# ZATININHO_V_1.net
KiCad netlist of a schematic drawn in EAGLE
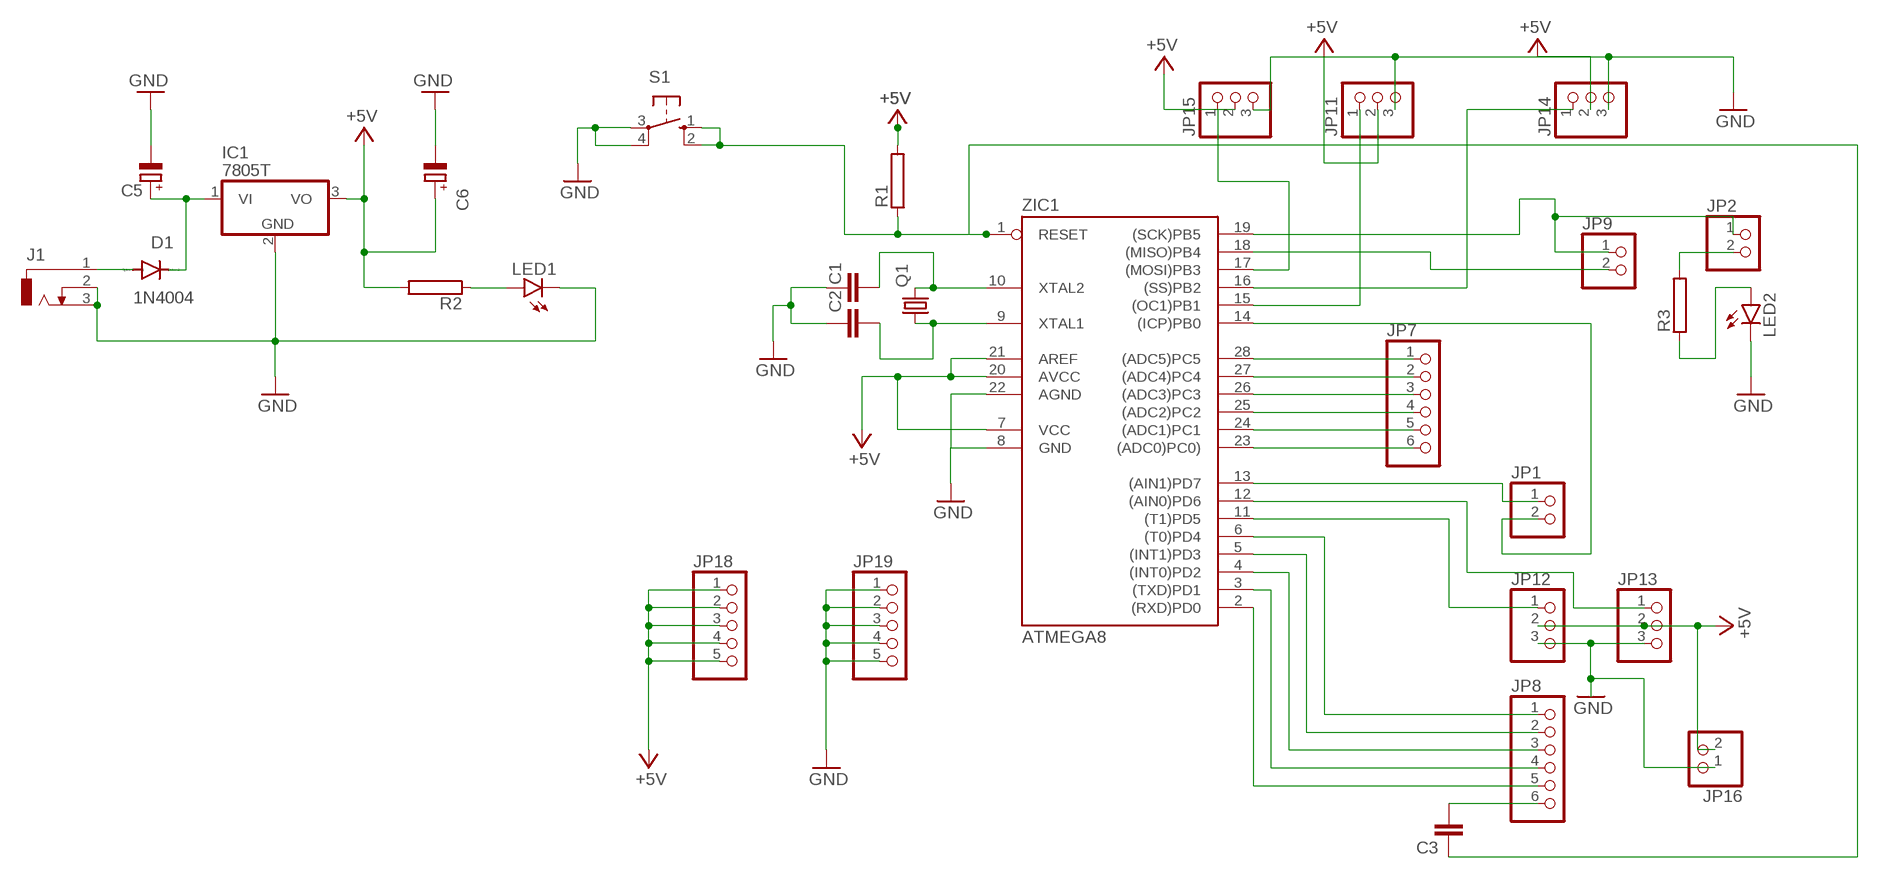
[diagram p0: schematic, sheet 1]

(export (version "E")
  (design (tool "Eeschema 10.0.6"))
  (components
    (comp (ref "C1")
      (value "C2.5/2")
      (footprint "eagle-import:C2.5-2")
      (libsource (lib "eagle-import") (part "C2.5/2"))
    )
    (comp (ref "C2")
      (value "C2.5/2")
      (footprint "eagle-import:C2.5-2")
      (libsource (lib "eagle-import") (part "C2.5/2"))
    )
    (comp (ref "C3")
      (value "C2,5-3")
      (footprint "eagle-import:C2.5-3")
      (libsource (lib "eagle-import") (part "C2,5-3"))
    )
    (comp (ref "C5")
      (value "CPOL-EUE2,5-6E")
      (footprint "eagle-import:E2,5-6E")
      (libsource (lib "eagle-import") (part "CPOL-EUE2,5-6E"))
    )
    (comp (ref "C6")
      (value "CPOL-EUE2,5-6E")
      (footprint "eagle-import:E2,5-6E")
      (libsource (lib "eagle-import") (part "CPOL-EUE2,5-6E"))
    )
    (comp (ref "D1")
      (value "1N4004")
      (footprint "eagle-import:DO41-10")
      (libsource (lib "eagle-import") (part "1N4004"))
    )
    (comp (ref "IC1")
      (value "7805T")
      (footprint "eagle-import:TO220H")
      (libsource (lib "eagle-import") (part "78T05"))
    )
    (comp (ref "J1")
      (value "DCJ0303")
      (footprint "eagle-import:DCJ0303")
      (libsource (lib "eagle-import") (part "DCJ0303"))
    )
    (comp (ref "JP1")
      (value "PINHD-1X2")
      (footprint "eagle-import:1X02")
      (libsource (lib "eagle-import") (part "PINHD-1X2"))
    )
    (comp (ref "JP2")
      (value "PINHD-1X2")
      (footprint "eagle-import:1X02")
      (libsource (lib "eagle-import") (part "PINHD-1X2"))
    )
    (comp (ref "JP7")
      (value "PINHD-1X6")
      (footprint "eagle-import:1X06")
      (libsource (lib "eagle-import") (part "PINHD-1X6"))
    )
    (comp (ref "JP8")
      (value "PINHD-1X6")
      (footprint "eagle-import:1X06")
      (libsource (lib "eagle-import") (part "PINHD-1X6"))
    )
    (comp (ref "JP9")
      (value "PINHD-1X2")
      (footprint "eagle-import:1X02")
      (libsource (lib "eagle-import") (part "PINHD-1X2"))
    )
    (comp (ref "JP11")
      (value "PINHD-1X3")
      (footprint "eagle-import:1X03")
      (libsource (lib "eagle-import") (part "PINHD-1X3"))
    )
    (comp (ref "JP12")
      (value "PINHD-1X3")
      (footprint "eagle-import:1X03")
      (libsource (lib "eagle-import") (part "PINHD-1X3"))
    )
    (comp (ref "JP13")
      (value "PINHD-1X3")
      (footprint "eagle-import:1X03")
      (libsource (lib "eagle-import") (part "PINHD-1X3"))
    )
    (comp (ref "JP14")
      (value "PINHD-1X3")
      (footprint "eagle-import:1X03")
      (libsource (lib "eagle-import") (part "PINHD-1X3"))
    )
    (comp (ref "JP15")
      (value "PINHD-1X3")
      (footprint "eagle-import:1X03")
      (libsource (lib "eagle-import") (part "PINHD-1X3"))
    )
    (comp (ref "JP16")
      (value "PINHD-1X2")
      (footprint "eagle-import:1X02")
      (libsource (lib "eagle-import") (part "PINHD-1X2"))
    )
    (comp (ref "JP18")
      (value "PINHD-1X5")
      (footprint "eagle-import:1X05")
      (libsource (lib "eagle-import") (part "PINHD-1X5"))
    )
    (comp (ref "JP19")
      (value "PINHD-1X5")
      (footprint "eagle-import:1X05")
      (libsource (lib "eagle-import") (part "PINHD-1X5"))
    )
    (comp (ref "LED1")
      (value "LED5MM")
      (footprint "eagle-import:LED5MM")
      (libsource (lib "eagle-import") (part "LED5MM"))
    )
    (comp (ref "LED2")
      (value "LED5MM")
      (footprint "eagle-import:LED5MM")
      (libsource (lib "eagle-import") (part "LED5MM"))
    )
    (comp (ref "Q1")
      (value "CRYSTALHC49U-V")
      (footprint "eagle-import:HC49U-V")
      (libsource (lib "eagle-import") (part "CRYSTALHC49U-V"))
    )
    (comp (ref "R1")
      (value "RRS1/4")
      (footprint "eagle-import:RS1_4")
      (fields (field (name "MF") "OHMITE") (field (name "MPN") "RRS1K0"))
      (libsource (lib "eagle-import") (part "RRS1/4"))
    )
    (comp (ref "R2")
      (value "RRS1/4")
      (footprint "eagle-import:RS1_4")
      (fields (field (name "MF") "OHMITE") (field (name "MPN") "RRS1K0"))
      (libsource (lib "eagle-import") (part "RRS1/4"))
    )
    (comp (ref "R3")
      (value "RRS1/4")
      (footprint "eagle-import:RS1_4")
      (fields (field (name "MF") "OHMITE") (field (name "MPN") "RRS1K0"))
      (libsource (lib "eagle-import") (part "RRS1/4"))
    )
    (comp (ref "S1")
      (value "10-XX")
      (footprint "eagle-import:B3F-10XX")
      (fields (field (name "MPN") "B3F-1000"))
      (libsource (lib "eagle-import") (part "10-XX"))
    )
    (comp (ref "ZIC1")
      (value "ATMEGA8")
      (footprint "eagle-import:DIL28-3")
      (libsource (lib "eagle-import") (part "AT90S4433P"))
    )
  )
  (nets
    (net (code "1") (name "+5V") (class "Default")
      (node (ref "C6") (pin "+") (pinfunction "+_+") (pintype "passive"))
      (node (ref "IC1") (pin "3") (pinfunction "VO_3") (pintype "passive"))
      (node (ref "JP11") (pin "2") (pinfunction "2_2") (pintype "passive"))
      (node (ref "JP12") (pin "2") (pinfunction "2_2") (pintype "passive"))
      (node (ref "JP13") (pin "2") (pinfunction "2_2") (pintype "passive"))
      (node (ref "JP14") (pin "2") (pinfunction "2_2") (pintype "passive"))
      (node (ref "JP15") (pin "2") (pinfunction "2_2") (pintype "passive"))
      (node (ref "JP16") (pin "2") (pinfunction "2_2") (pintype "passive"))
      (node (ref "JP18") (pin "1") (pinfunction "1_1") (pintype "passive"))
      (node (ref "JP18") (pin "2") (pinfunction "2_2") (pintype "passive"))
      (node (ref "JP18") (pin "3") (pinfunction "3_3") (pintype "passive"))
      (node (ref "JP18") (pin "4") (pinfunction "4_4") (pintype "passive"))
      (node (ref "JP18") (pin "5") (pinfunction "5_5") (pintype "passive"))
      (node (ref "R1") (pin "2") (pinfunction "2_2") (pintype "passive"))
      (node (ref "R2") (pin "2") (pinfunction "2_2") (pintype "passive"))
      (node (ref "ZIC1") (pin "20") (pinfunction "AVCC_20") (pintype "power_in"))
      (node (ref "ZIC1") (pin "21") (pinfunction "AREF_21") (pintype "passive"))
      (node (ref "ZIC1") (pin "7") (pinfunction "VCC_7") (pintype "power_in"))
    )
    (net (code "2") (name "GND") (class "Default")
      (node (ref "C1") (pin "1") (pinfunction "1_1") (pintype "passive"))
      (node (ref "C2") (pin "1") (pinfunction "1_1") (pintype "passive"))
      (node (ref "C5") (pin "-") (pinfunction "-_-") (pintype "passive"))
      (node (ref "C6") (pin "-") (pinfunction "-_-") (pintype "passive"))
      (node (ref "IC1") (pin "2") (pinfunction "GND_2") (pintype "passive"))
      (node (ref "J1") (pin "2") (pinfunction "2_2") (pintype "passive"))
      (node (ref "J1") (pin "3") (pinfunction "3_3") (pintype "passive"))
      (node (ref "JP11") (pin "3") (pinfunction "3_3") (pintype "passive"))
      (node (ref "JP12") (pin "3") (pinfunction "3_3") (pintype "passive"))
      (node (ref "JP13") (pin "3") (pinfunction "3_3") (pintype "passive"))
      (node (ref "JP14") (pin "3") (pinfunction "3_3") (pintype "passive"))
      (node (ref "JP15") (pin "3") (pinfunction "3_3") (pintype "passive"))
      (node (ref "JP16") (pin "1") (pinfunction "1_1") (pintype "passive"))
      (node (ref "JP19") (pin "1") (pinfunction "1_1") (pintype "passive"))
      (node (ref "JP19") (pin "2") (pinfunction "2_2") (pintype "passive"))
      (node (ref "JP19") (pin "3") (pinfunction "3_3") (pintype "passive"))
      (node (ref "JP19") (pin "4") (pinfunction "4_4") (pintype "passive"))
      (node (ref "JP19") (pin "5") (pinfunction "5_5") (pintype "passive"))
      (node (ref "LED1") (pin "K") (pinfunction "C_K") (pintype "passive"))
      (node (ref "LED2") (pin "K") (pinfunction "C_K") (pintype "passive"))
      (node (ref "S1") (pin "3") (pinfunction "P_3") (pintype "passive"))
      (node (ref "S1") (pin "4") (pinfunction "P1_4") (pintype "passive"))
      (node (ref "ZIC1") (pin "22") (pinfunction "AGND_22") (pintype "power_in"))
      (node (ref "ZIC1") (pin "8") (pinfunction "GND_8") (pintype "power_in"))
    )
    (net (code "3") (name "Net-(C3-Pad2)") (class "Default")
      (node (ref "C3") (pin "2") (pinfunction "2_2") (pintype "passive"))
      (node (ref "JP8") (pin "6") (pinfunction "6_6") (pintype "passive"))
    )
    (net (code "4") (name "Net-(D1-PadA)") (class "Default")
      (node (ref "D1") (pin "A") (pinfunction "A_A") (pintype "passive"))
      (node (ref "J1") (pin "1") (pinfunction "1_1") (pintype "passive"))
    )
    (net (code "5") (name "Net-(IC1-VI)") (class "Default")
      (node (ref "C5") (pin "+") (pinfunction "+_+") (pintype "passive"))
      (node (ref "D1") (pin "C") (pinfunction "C_C") (pintype "passive"))
      (node (ref "IC1") (pin "1") (pinfunction "VI_1") (pintype "input"))
    )
    (net (code "6") (name "Net-(JP2-Pad2)") (class "Default")
      (node (ref "JP2") (pin "2") (pinfunction "2_2") (pintype "passive"))
      (node (ref "R3") (pin "2") (pinfunction "2_2") (pintype "passive"))
    )
    (net (code "7") (name "Net-(LED1-PadA)") (class "Default")
      (node (ref "LED1") (pin "A") (pinfunction "A_A") (pintype "passive"))
      (node (ref "R2") (pin "1") (pinfunction "1_1") (pintype "passive"))
    )
    (net (code "8") (name "Net-(LED2-PadA)") (class "Default")
      (node (ref "LED2") (pin "A") (pinfunction "A_A") (pintype "passive"))
      (node (ref "R3") (pin "1") (pinfunction "1_1") (pintype "passive"))
    )
    (net (code "9") (name "Net-(S1-S)") (class "Default")
      (node (ref "C3") (pin "1") (pinfunction "1_1") (pintype "passive"))
      (node (ref "R1") (pin "1") (pinfunction "1_1") (pintype "passive"))
      (node (ref "S1") (pin "1") (pinfunction "S_1") (pintype "passive"))
      (node (ref "S1") (pin "2") (pinfunction "S1_2") (pintype "passive"))
      (node (ref "ZIC1") (pin "1") (pinfunction "RESET_1") (pintype "input"))
    )
    (net (code "10") (name "Net-(ZIC1-(ADC0)PC0))") (class "Default")
      (node (ref "JP7") (pin "6") (pinfunction "6_6") (pintype "passive"))
      (node (ref "ZIC1") (pin "23") (pinfunction "(ADC0)PC0)_23") (pintype "bidirectional"))
    )
    (net (code "11") (name "Net-(ZIC1-(ADC1)PC1)") (class "Default")
      (node (ref "JP7") (pin "5") (pinfunction "5_5") (pintype "passive"))
      (node (ref "ZIC1") (pin "24") (pinfunction "(ADC1)PC1_24") (pintype "bidirectional"))
    )
    (net (code "12") (name "Net-(ZIC1-(ADC2)PC2)") (class "Default")
      (node (ref "JP7") (pin "4") (pinfunction "4_4") (pintype "passive"))
      (node (ref "ZIC1") (pin "25") (pinfunction "(ADC2)PC2_25") (pintype "bidirectional"))
    )
    (net (code "13") (name "Net-(ZIC1-(ADC3)PC3)") (class "Default")
      (node (ref "JP7") (pin "3") (pinfunction "3_3") (pintype "passive"))
      (node (ref "ZIC1") (pin "26") (pinfunction "(ADC3)PC3_26") (pintype "bidirectional"))
    )
    (net (code "14") (name "Net-(ZIC1-(ADC4)PC4)") (class "Default")
      (node (ref "JP7") (pin "2") (pinfunction "2_2") (pintype "passive"))
      (node (ref "ZIC1") (pin "27") (pinfunction "(ADC4)PC4_27") (pintype "bidirectional"))
    )
    (net (code "15") (name "Net-(ZIC1-(ADC5)PC5)") (class "Default")
      (node (ref "JP7") (pin "1") (pinfunction "1_1") (pintype "passive"))
      (node (ref "ZIC1") (pin "28") (pinfunction "(ADC5)PC5_28") (pintype "bidirectional"))
    )
    (net (code "16") (name "Net-(ZIC1-(AIN0)PD6)") (class "Default")
      (node (ref "JP13") (pin "1") (pinfunction "1_1") (pintype "passive"))
      (node (ref "ZIC1") (pin "12") (pinfunction "(AIN0)PD6_12") (pintype "bidirectional"))
    )
    (net (code "17") (name "Net-(ZIC1-(AIN1)PD7)") (class "Default")
      (node (ref "JP1") (pin "1") (pinfunction "1_1") (pintype "passive"))
      (node (ref "ZIC1") (pin "13") (pinfunction "(AIN1)PD7_13") (pintype "bidirectional"))
    )
    (net (code "18") (name "Net-(ZIC1-(ICP)PB0)") (class "Default")
      (node (ref "JP1") (pin "2") (pinfunction "2_2") (pintype "passive"))
      (node (ref "ZIC1") (pin "14") (pinfunction "(ICP)PB0_14") (pintype "bidirectional"))
    )
    (net (code "19") (name "Net-(ZIC1-(INT0)PD2)") (class "Default")
      (node (ref "JP8") (pin "3") (pinfunction "3_3") (pintype "passive"))
      (node (ref "ZIC1") (pin "4") (pinfunction "(INT0)PD2_4") (pintype "bidirectional"))
    )
    (net (code "20") (name "Net-(ZIC1-(INT1)PD3)") (class "Default")
      (node (ref "JP8") (pin "2") (pinfunction "2_2") (pintype "passive"))
      (node (ref "ZIC1") (pin "5") (pinfunction "(INT1)PD3_5") (pintype "bidirectional"))
    )
    (net (code "21") (name "Net-(ZIC1-(MISO)PB4)") (class "Default")
      (node (ref "JP9") (pin "2") (pinfunction "2_2") (pintype "passive"))
      (node (ref "ZIC1") (pin "18") (pinfunction "(MISO)PB4_18") (pintype "bidirectional"))
    )
    (net (code "22") (name "Net-(ZIC1-(MOSI)PB3)") (class "Default")
      (node (ref "JP15") (pin "1") (pinfunction "1_1") (pintype "passive"))
      (node (ref "ZIC1") (pin "17") (pinfunction "(MOSI)PB3_17") (pintype "bidirectional"))
    )
    (net (code "23") (name "Net-(ZIC1-(OC1)PB1)") (class "Default")
      (node (ref "JP11") (pin "1") (pinfunction "1_1") (pintype "passive"))
      (node (ref "ZIC1") (pin "15") (pinfunction "(OC1)PB1_15") (pintype "bidirectional"))
    )
    (net (code "24") (name "Net-(ZIC1-(RXD)PD0)") (class "Default")
      (node (ref "JP8") (pin "5") (pinfunction "5_5") (pintype "passive"))
      (node (ref "ZIC1") (pin "2") (pinfunction "(RXD)PD0_2") (pintype "bidirectional"))
    )
    (net (code "25") (name "Net-(ZIC1-(SCK)PB5)") (class "Default")
      (node (ref "JP2") (pin "1") (pinfunction "1_1") (pintype "passive"))
      (node (ref "JP9") (pin "1") (pinfunction "1_1") (pintype "passive"))
      (node (ref "ZIC1") (pin "19") (pinfunction "(SCK)PB5_19") (pintype "bidirectional"))
    )
    (net (code "26") (name "Net-(ZIC1-(SS)PB2)") (class "Default")
      (node (ref "JP14") (pin "1") (pinfunction "1_1") (pintype "passive"))
      (node (ref "ZIC1") (pin "16") (pinfunction "(SS)PB2_16") (pintype "bidirectional"))
    )
    (net (code "27") (name "Net-(ZIC1-(T0)PD4)") (class "Default")
      (node (ref "JP8") (pin "1") (pinfunction "1_1") (pintype "passive"))
      (node (ref "ZIC1") (pin "6") (pinfunction "(T0)PD4_6") (pintype "bidirectional"))
    )
    (net (code "28") (name "Net-(ZIC1-(T1)PD5)") (class "Default")
      (node (ref "JP12") (pin "1") (pinfunction "1_1") (pintype "passive"))
      (node (ref "ZIC1") (pin "11") (pinfunction "(T1)PD5_11") (pintype "bidirectional"))
    )
    (net (code "29") (name "Net-(ZIC1-(TXD)PD1)") (class "Default")
      (node (ref "JP8") (pin "4") (pinfunction "4_4") (pintype "passive"))
      (node (ref "ZIC1") (pin "3") (pinfunction "(TXD)PD1_3") (pintype "bidirectional"))
    )
    (net (code "30") (name "Net-(ZIC1-XTAL1)") (class "Default")
      (node (ref "C2") (pin "2") (pinfunction "2_2") (pintype "passive"))
      (node (ref "Q1") (pin "1") (pinfunction "1_1") (pintype "passive"))
      (node (ref "ZIC1") (pin "9") (pinfunction "XTAL1_9") (pintype "bidirectional"))
    )
    (net (code "31") (name "Net-(ZIC1-XTAL2)") (class "Default")
      (node (ref "C1") (pin "2") (pinfunction "2_2") (pintype "passive"))
      (node (ref "Q1") (pin "2") (pinfunction "2_2") (pintype "passive"))
      (node (ref "ZIC1") (pin "10") (pinfunction "XTAL2_10") (pintype "bidirectional"))
    )
  )
)
